# LP-LED.net
KiCad netlist of a schematic drawn in EAGLE
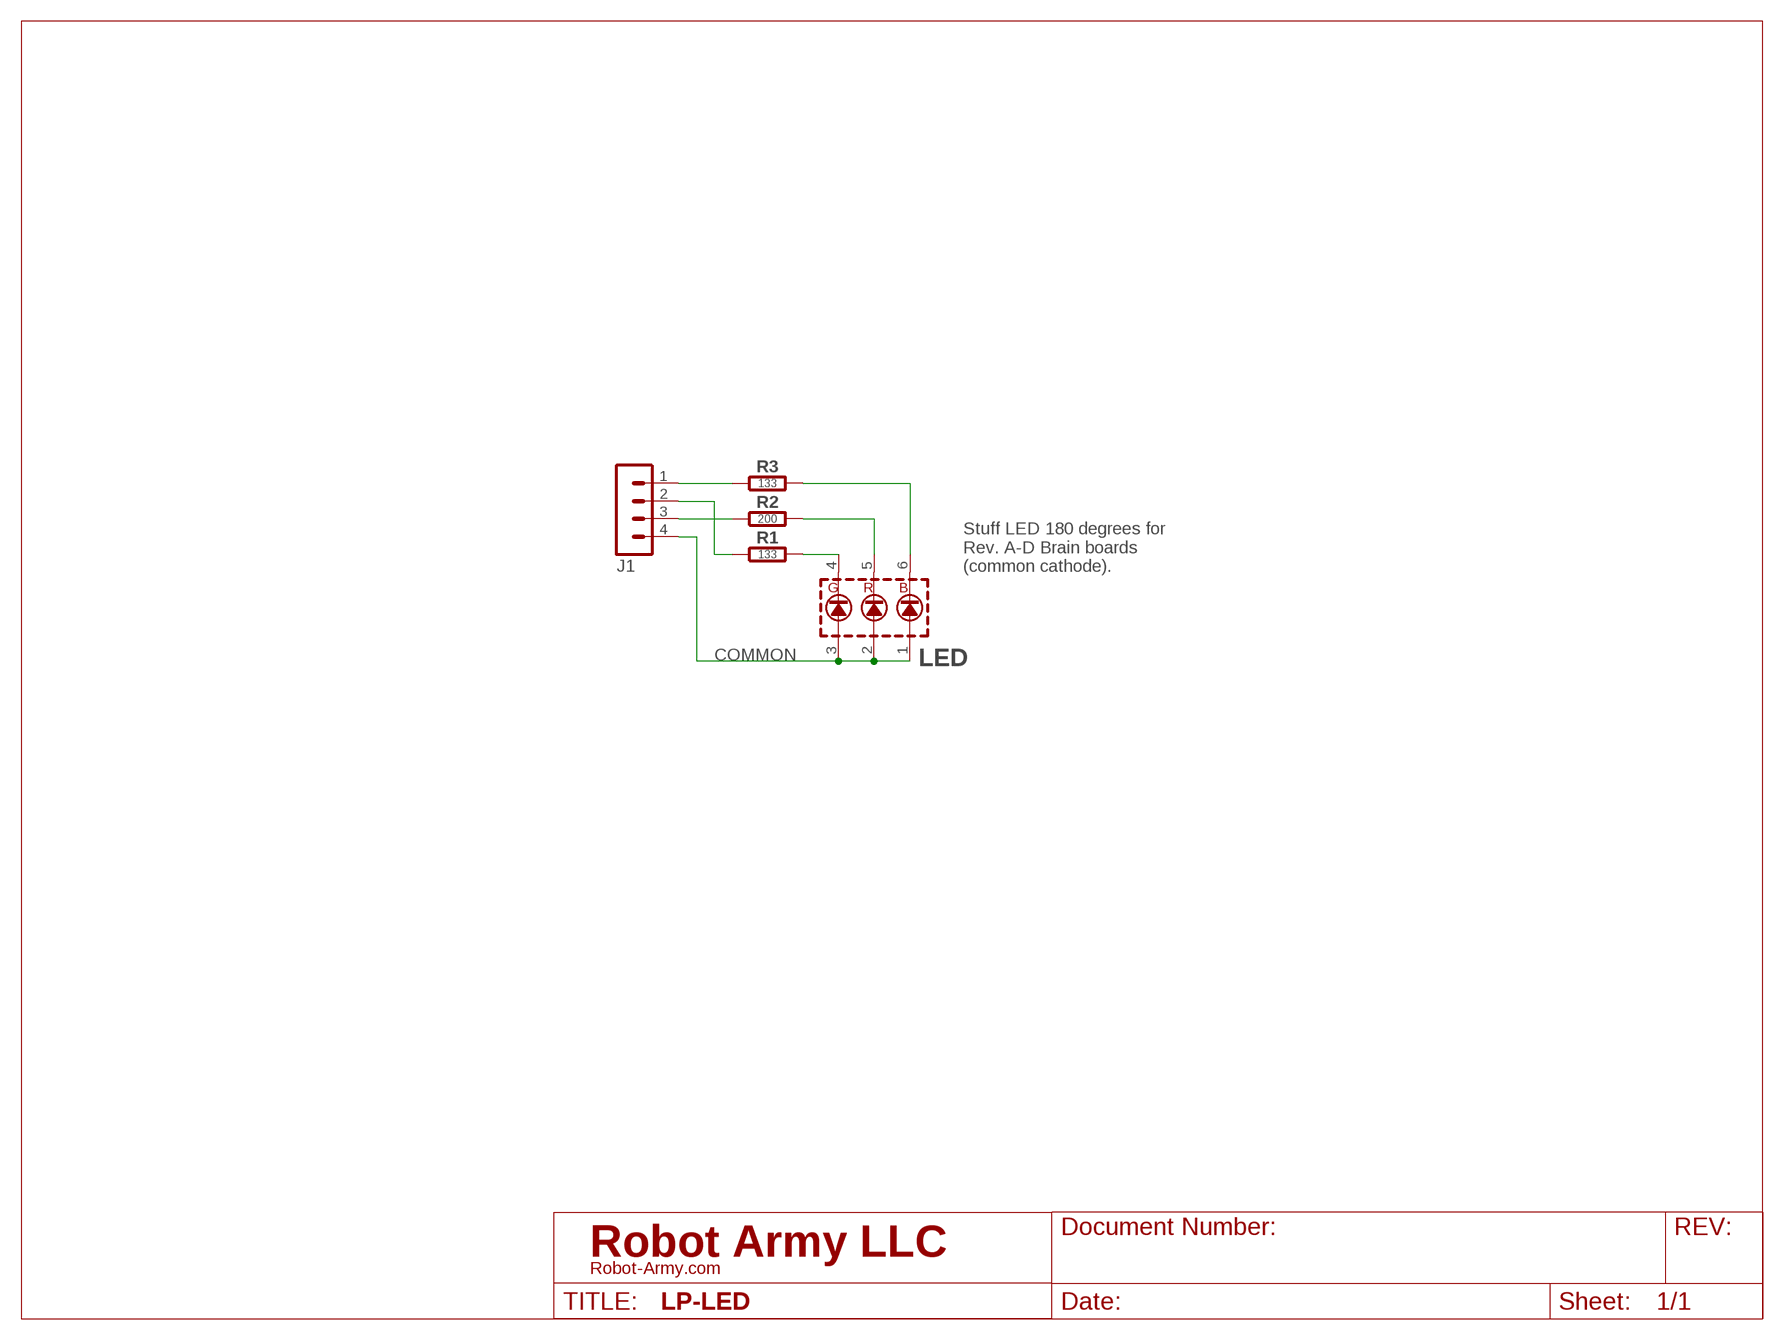
[diagram p0: schematic, sheet 1]

(export (version "E")
  (design (tool "Eeschema 10.0.6"))
  (components
    (comp (ref "J1")
      (value "MA04-1")
      (footprint "eagle-import:MA04-1")
      (libsource (lib "eagle-import") (part "MA04-1"))
    )
    (comp (ref "LED")
      (value "RGB_INDIVPLCC-6")
      (footprint "eagle-import:PLCC-6")
      (libsource (lib "eagle-import") (part "RGB_INDIVPLCC-6"))
    )
    (comp (ref "R1")
      (value "133")
      (footprint "eagle-import:0805")
      (libsource (lib "eagle-import") (part "RESISTOR0805"))
    )
    (comp (ref "R2")
      (value "200")
      (footprint "eagle-import:0805")
      (libsource (lib "eagle-import") (part "RESISTOR0805"))
    )
    (comp (ref "R3")
      (value "133")
      (footprint "eagle-import:0805")
      (libsource (lib "eagle-import") (part "RESISTOR0805"))
    )
  )
  (nets
    (net (code "1") (name "/COMMON") (class "Default")
      (node (ref "J1") (pin "4") (pinfunction "4_4") (pintype "passive"))
      (node (ref "LED") (pin "1") (pinfunction "AB_1") (pintype "bidirectional"))
      (node (ref "LED") (pin "2") (pinfunction "AR_2") (pintype "bidirectional"))
      (node (ref "LED") (pin "3") (pinfunction "AG_3") (pintype "bidirectional"))
    )
    (net (code "2") (name "Net-(J1-Pad1)") (class "Default")
      (node (ref "J1") (pin "1") (pinfunction "1_1") (pintype "passive"))
      (node (ref "R3") (pin "1") (pinfunction "1_1") (pintype "passive"))
    )
    (net (code "3") (name "Net-(J1-Pad2)") (class "Default")
      (node (ref "J1") (pin "2") (pinfunction "2_2") (pintype "passive"))
      (node (ref "R1") (pin "1") (pinfunction "1_1") (pintype "passive"))
    )
    (net (code "4") (name "Net-(J1-Pad3)") (class "Default")
      (node (ref "J1") (pin "3") (pinfunction "3_3") (pintype "passive"))
      (node (ref "R2") (pin "1") (pinfunction "1_1") (pintype "passive"))
    )
    (net (code "5") (name "Net-(LED-KB)") (class "Default")
      (node (ref "LED") (pin "6") (pinfunction "KB_6") (pintype "bidirectional"))
      (node (ref "R3") (pin "2") (pinfunction "2_2") (pintype "passive"))
    )
    (net (code "6") (name "Net-(LED-KG)") (class "Default")
      (node (ref "LED") (pin "4") (pinfunction "KG_4") (pintype "bidirectional"))
      (node (ref "R1") (pin "2") (pinfunction "2_2") (pintype "passive"))
    )
    (net (code "7") (name "Net-(LED-KR)") (class "Default")
      (node (ref "LED") (pin "5") (pinfunction "KR_5") (pintype "bidirectional"))
      (node (ref "R2") (pin "2") (pinfunction "2_2") (pintype "passive"))
    )
  )
)
